# untitled.net
KiCad netlist of a schematic drawn in EAGLE
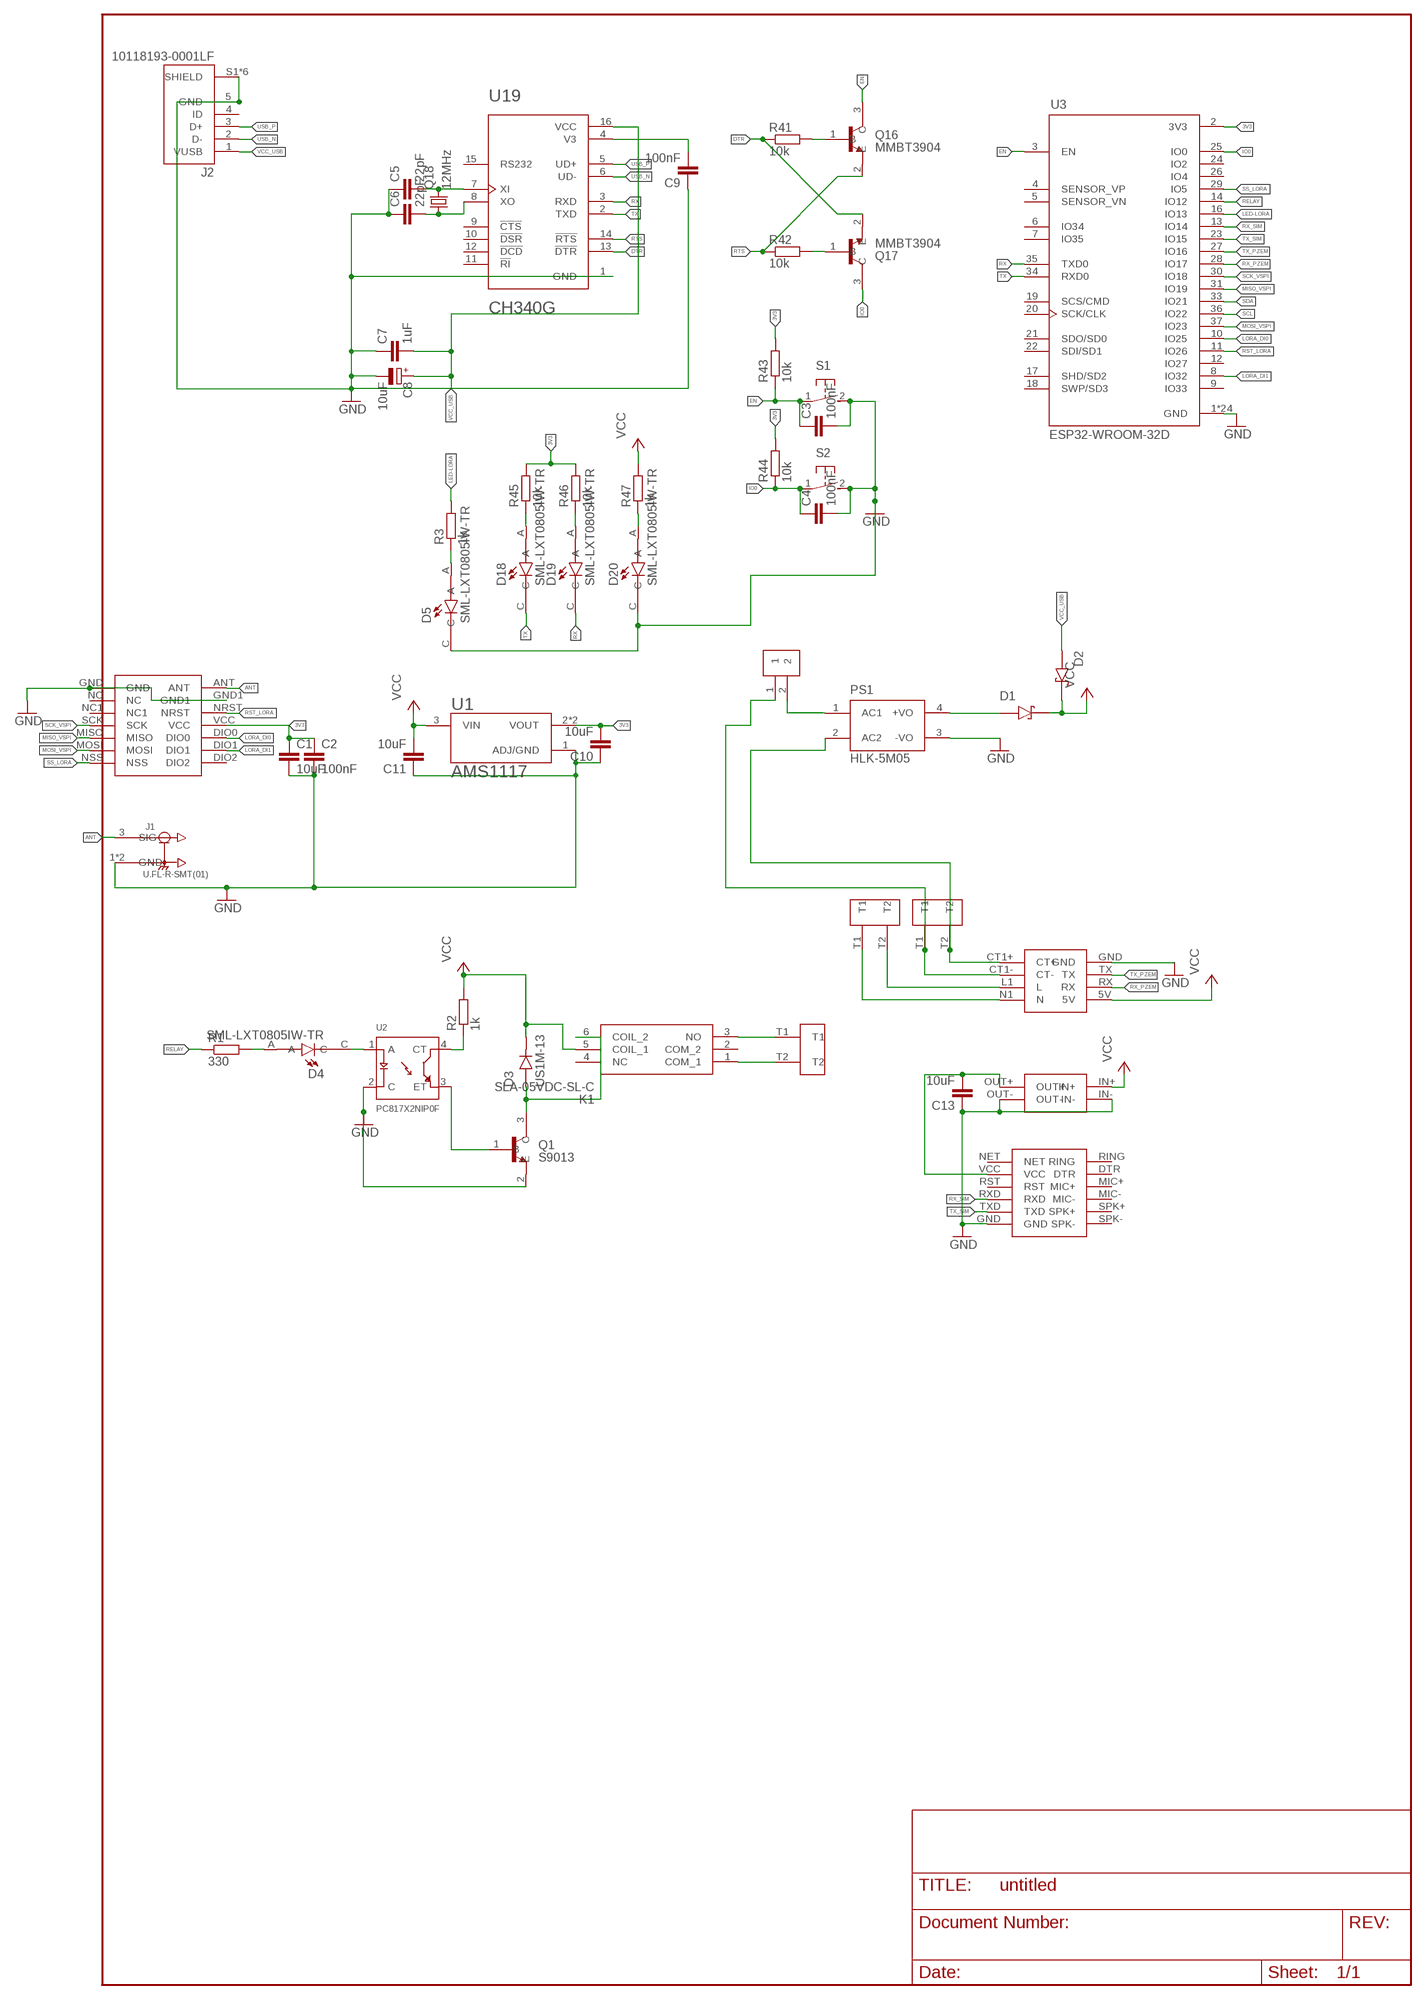
[diagram p0: schematic, sheet 1]

(export (version "E")
  (design (tool "Eeschema 10.0.6"))
  (components
    (comp (ref "C1")
      (value "10uF")
      (footprint "eagle-import:C0805K")
      (libsource (lib "eagle-import") (part "C-EUC0805K"))
    )
    (comp (ref "C2")
      (value "100nF")
      (footprint "eagle-import:C0805K")
      (libsource (lib "eagle-import") (part "C-EUC0805K"))
    )
    (comp (ref "C3")
      (value "100nF")
      (footprint "eagle-import:C0805K")
      (libsource (lib "eagle-import") (part "C-EUC0805K"))
    )
    (comp (ref "C4")
      (value "100nF")
      (footprint "eagle-import:C0805K")
      (libsource (lib "eagle-import") (part "C-EUC0805K"))
    )
    (comp (ref "C5")
      (value "22pF")
      (footprint "eagle-import:C0805K")
      (libsource (lib "eagle-import") (part "C-EUC0805K"))
    )
    (comp (ref "C6")
      (value "22pF")
      (footprint "eagle-import:C0805K")
      (libsource (lib "eagle-import") (part "C-EUC0805K"))
    )
    (comp (ref "C7")
      (value "1uF")
      (footprint "eagle-import:C0805K")
      (libsource (lib "eagle-import") (part "C-EUC0805K"))
    )
    (comp (ref "C8")
      (value "10uF")
      (footprint "eagle-import:153CLV-0505")
      (libsource (lib "eagle-import") (part "CPOL-EU153CLV-0505"))
    )
    (comp (ref "C9")
      (value "100nF")
      (footprint "eagle-import:C0805K")
      (libsource (lib "eagle-import") (part "C-EUC0805K"))
    )
    (comp (ref "C10")
      (value "10uF")
      (footprint "eagle-import:C0805K")
      (libsource (lib "eagle-import") (part "C-EUC0805K"))
    )
    (comp (ref "C11")
      (value "10uF")
      (footprint "eagle-import:C0805K")
      (libsource (lib "eagle-import") (part "C-EUC0805K"))
    )
    (comp (ref "C13")
      (value "10uF")
      (footprint "eagle-import:C0805K")
      (libsource (lib "eagle-import") (part "C-EUC0805K"))
    )
    (comp (ref "D1")
      (value "1N5819HW-7")
      (footprint "eagle-import:SOD3715X145N")
      (fields (field (name "MF") "Diodes Inc."))
      (libsource (lib "eagle-import") (part "1N5819HW-7"))
    )
    (comp (ref "D2")
      (value "1N5819HW-7")
      (footprint "eagle-import:SOD3715X145N")
      (fields (field (name "MF") "Diodes Inc."))
      (libsource (lib "eagle-import") (part "1N5819HW-7"))
    )
    (comp (ref "D3")
      (value "US1M-13")
      (footprint "eagle-import:DIOM5226X240N")
      (fields (field (name "MF") "Diodes Incorporated"))
      (libsource (lib "eagle-import") (part "US1M-13"))
    )
    (comp (ref "D4")
      (value "SML-LXT0805IW-TR")
      (footprint "eagle-import:LEDC2012X120N")
      (fields (field (name "MF") "Lumex Opto/Components"))
      (libsource (lib "eagle-import") (part "SML-LXT0805IW-TR"))
    )
    (comp (ref "D5")
      (value "SML-LXT0805IW-TR")
      (footprint "eagle-import:LEDC2012X120N")
      (fields (field (name "MF") "Lumex Opto/Components"))
      (libsource (lib "eagle-import") (part "SML-LXT0805IW-TR"))
    )
    (comp (ref "D18")
      (value "SML-LXT0805IW-TR")
      (footprint "eagle-import:LEDC2012X120N")
      (fields (field (name "MF") "Lumex Opto/Components"))
      (libsource (lib "eagle-import") (part "SML-LXT0805IW-TR"))
    )
    (comp (ref "D19")
      (value "SML-LXT0805IW-TR")
      (footprint "eagle-import:LEDC2012X120N")
      (fields (field (name "MF") "Lumex Opto/Components"))
      (libsource (lib "eagle-import") (part "SML-LXT0805IW-TR"))
    )
    (comp (ref "D20")
      (value "SML-LXT0805IW-TR")
      (footprint "eagle-import:LEDC2012X120N")
      (fields (field (name "MF") "Lumex Opto/Components"))
      (libsource (lib "eagle-import") (part "SML-LXT0805IW-TR"))
    )
    (comp (ref "FUSE-KOTAK1")
      (value "FUSE-KOTAK")
      (footprint "eagle-import:FUSE-KOTAK")
      (libsource (lib "eagle-import") (part "FUSE-KOTAK"))
    )
    (comp (ref "J1")
      (value "U.FL-R-SMT(01)")
      (footprint "eagle-import:HRS_U.FL-R-SMT(01)")
      (fields (field (name "MF") "Hirose"))
      (libsource (lib "eagle-import") (part "U.FL-R-SMT(01)"))
    )
    (comp (ref "J2")
      (value "10118193-0001LF")
      (footprint "eagle-import:FCI_10118193-0001LF")
      (fields (field (name "MF") "FCI"))
      (libsource (lib "eagle-import") (part "10118193-0001LF"))
    )
    (comp (ref "K1")
      (value "SLA-05VDC-SL-C")
      (footprint "eagle-import:SLA05VDCSLC")
      (libsource (lib "eagle-import") (part "SLA-05VDC-SL-C"))
    )
    (comp (ref "LORA-NICERF-V1")
      (value "LORA-NICERF-V2")
      (footprint "eagle-import:LORA-NICERF-V2")
      (libsource (lib "eagle-import") (part "LORA-NICERF-V2"))
    )
    (comp (ref "MINI1")
      (value "MINI360")
      (footprint "eagle-import:MINI360")
      (libsource (lib "eagle-import") (part "MINI360"))
    )
    (comp (ref "PS1")
      (value "HLK-5M05")
      (footprint "eagle-import:CONV_HLK-5M05")
      (fields (field (name "MF") "Hi-link"))
      (libsource (lib "eagle-import") (part "HLK-5M05"))
    )
    (comp (ref "PZEM004T1")
      (value "PZEM004T")
      (footprint "eagle-import:PZEM004T")
      (libsource (lib "eagle-import") (part "PZEM004T"))
    )
    (comp (ref "Q1")
      (value "S9013")
      (footprint "eagle-import:SOT95P240X120-3N")
      (fields (field (name "MF") "JCET"))
      (libsource (lib "eagle-import") (part "S9013"))
    )
    (comp (ref "Q16")
      (value "MMBT3904")
      (footprint "eagle-import:SOT95P240X120-3N")
      (fields (field (name "MF") "ON Semiconductor"))
      (libsource (lib "eagle-import") (part "MMBT3904"))
    )
    (comp (ref "Q17")
      (value "MMBT3904")
      (footprint "eagle-import:SOT95P240X120-3N")
      (fields (field (name "MF") "ON Semiconductor"))
      (libsource (lib "eagle-import") (part "MMBT3904"))
    )
    (comp (ref "Q18")
      (value "12MHz")
      (footprint "eagle-import:SM49")
      (libsource (lib "eagle-import") (part "CRYSTALSM49"))
    )
    (comp (ref "R1")
      (value "330")
      (footprint "eagle-import:R0805")
      (libsource (lib "eagle-import") (part "R-EU_R0805"))
    )
    (comp (ref "R2")
      (value "1k")
      (footprint "eagle-import:R0805")
      (libsource (lib "eagle-import") (part "R-EU_R0805"))
    )
    (comp (ref "R3")
      (value "1k")
      (footprint "eagle-import:R0805")
      (libsource (lib "eagle-import") (part "R-EU_R0805"))
    )
    (comp (ref "R41")
      (value "10k")
      (footprint "eagle-import:R0805")
      (libsource (lib "eagle-import") (part "R-EU_R0805"))
    )
    (comp (ref "R42")
      (value "10k")
      (footprint "eagle-import:R0805")
      (libsource (lib "eagle-import") (part "R-EU_R0805"))
    )
    (comp (ref "R43")
      (value "10k")
      (footprint "eagle-import:R0805")
      (libsource (lib "eagle-import") (part "R-EU_R0805"))
    )
    (comp (ref "R44")
      (value "10k")
      (footprint "eagle-import:R0805")
      (libsource (lib "eagle-import") (part "R-EU_R0805"))
    )
    (comp (ref "R45")
      (value "10k")
      (footprint "eagle-import:R0805")
      (libsource (lib "eagle-import") (part "R-EU_R0805"))
    )
    (comp (ref "R46")
      (value "10k")
      (footprint "eagle-import:R0805")
      (libsource (lib "eagle-import") (part "R-EU_R0805"))
    )
    (comp (ref "R47")
      (value "1k")
      (footprint "eagle-import:R0805")
      (libsource (lib "eagle-import") (part "R-EU_R0805"))
    )
    (comp (ref "S1")
      (value "31-XX")
      (footprint "eagle-import:B3F-31XX")
      (fields (field (name "MPN") "B3F-3100"))
      (libsource (lib "eagle-import") (part "31-XX"))
    )
    (comp (ref "S2")
      (value "31-XX")
      (footprint "eagle-import:B3F-31XX")
      (fields (field (name "MPN") "B3F-3100"))
      (libsource (lib "eagle-import") (part "31-XX"))
    )
    (comp (ref "SIM800L1")
      (value "SIM800L")
      (footprint "eagle-import:SIM800L")
      (libsource (lib "eagle-import") (part "SIM800L"))
    )
    (comp (ref "TB7.2")
      (value "TB7.62")
      (footprint "eagle-import:TB7.62")
      (libsource (lib "eagle-import") (part "TB7.62"))
    )
    (comp (ref "TB7.3")
      (value "TB7.62")
      (footprint "eagle-import:TB7.62")
      (libsource (lib "eagle-import") (part "TB7.62"))
    )
    (comp (ref "TB7.4")
      (value "TB7.62")
      (footprint "eagle-import:TB7.62")
      (libsource (lib "eagle-import") (part "TB7.62"))
    )
    (comp (ref "U1")
      (value "AMS1117")
      (footprint "eagle-import:SOT229P700X180-4N")
      (fields (field (name "MF") "Advanced Monolithic Systems"))
      (libsource (lib "eagle-import") (part "AMS1117"))
    )
    (comp (ref "U2")
      (value "PC817X2NIP0F")
      (footprint "eagle-import:SOT254P975X400-4N")
      (fields (field (name "MF") "Sharp Microelectronics"))
      (libsource (lib "eagle-import") (part "PC817X2NIP0F"))
    )
    (comp (ref "U3")
      (value "ESP32-WROOM-32D")
      (footprint "eagle-import:MODULE_ESP32-WROOM-32D")
      (fields (field (name "MF") "Espressif Systems"))
      (libsource (lib "eagle-import") (part "ESP32-WROOM-32D"))
    )
    (comp (ref "U19")
      (value "CH340G")
      (footprint "eagle-import:SOIC127P600X180-16N")
      (fields (field (name "MF") "WCH") (field (name "MP") "Ch340G"))
      (libsource (lib "eagle-import") (part "CH340G"))
    )
  )
  (nets
    (net (code "1") (name "3V3") (class "Default")
      (node (ref "C1") (pin "1") (pinfunction "1_1") (pintype "passive"))
      (node (ref "C10") (pin "2") (pinfunction "2_2") (pintype "passive"))
      (node (ref "C2") (pin "1") (pinfunction "1_1") (pintype "passive"))
      (node (ref "LORA-NICERF-V1") (pin "VCC") (pinfunction "VCC_VCC") (pintype "bidirectional"))
      (node (ref "R43") (pin "2") (pinfunction "2_2") (pintype "passive"))
      (node (ref "R44") (pin "2") (pinfunction "2_2") (pintype "passive"))
      (node (ref "R45") (pin "2") (pinfunction "2_2") (pintype "passive"))
      (node (ref "R46") (pin "2") (pinfunction "2_2") (pintype "passive"))
      (node (ref "U1") (pin "2") (pinfunction "VOUT_2") (pintype "output"))
      (node (ref "U1") (pin "4") (pinfunction "VOUT_4") (pintype "output"))
      (node (ref "U3") (pin "2") (pinfunction "3V3_2") (pintype "power_in"))
    )
    (net (code "2") (name "ANT") (class "Default")
      (node (ref "J1") (pin "3") (pinfunction "SIG_3") (pintype "passive"))
      (node (ref "LORA-NICERF-V1") (pin "ANT") (pinfunction "ANT_ANT") (pintype "bidirectional"))
    )
    (net (code "3") (name "DTR") (class "Default")
      (node (ref "Q17") (pin "2") (pinfunction "E_2") (pintype "passive"))
      (node (ref "R41") (pin "1") (pinfunction "1_1") (pintype "passive"))
      (node (ref "U19") (pin "13") (pinfunction "~{DTR}_13") (pintype "output"))
    )
    (net (code "4") (name "EN") (class "Default")
      (node (ref "C3") (pin "1") (pinfunction "1_1") (pintype "passive"))
      (node (ref "Q16") (pin "3") (pinfunction "C_3") (pintype "passive"))
      (node (ref "R43") (pin "1") (pinfunction "1_1") (pintype "passive"))
      (node (ref "S1") (pin "1") (pinfunction "P_1") (pintype "passive"))
      (node (ref "U3") (pin "3") (pinfunction "EN_3") (pintype "input"))
    )
    (net (code "5") (name "GND") (class "Default")
      (node (ref "C1") (pin "2") (pinfunction "2_2") (pintype "passive"))
      (node (ref "C10") (pin "1") (pinfunction "1_1") (pintype "passive"))
      (node (ref "C11") (pin "1") (pinfunction "1_1") (pintype "passive"))
      (node (ref "C13") (pin "1") (pinfunction "1_1") (pintype "passive"))
      (node (ref "C2") (pin "2") (pinfunction "2_2") (pintype "passive"))
      (node (ref "C3") (pin "2") (pinfunction "2_2") (pintype "passive"))
      (node (ref "C4") (pin "2") (pinfunction "2_2") (pintype "passive"))
      (node (ref "C5") (pin "1") (pinfunction "1_1") (pintype "passive"))
      (node (ref "C6") (pin "1") (pinfunction "1_1") (pintype "passive"))
      (node (ref "C7") (pin "1") (pinfunction "1_1") (pintype "passive"))
      (node (ref "C8") (pin "-") (pinfunction "-_-") (pintype "passive"))
      (node (ref "C9") (pin "1") (pinfunction "1_1") (pintype "passive"))
      (node (ref "D20") (pin "C") (pinfunction "C_C") (pintype "passive"))
      (node (ref "D5") (pin "C") (pinfunction "C_C") (pintype "passive"))
      (node (ref "J1") (pin "1") (pinfunction "GND_1") (pintype "passive"))
      (node (ref "J1") (pin "2") (pinfunction "GND_2") (pintype "passive"))
      (node (ref "J2") (pin "5") (pinfunction "GND_5") (pintype "passive"))
      (node (ref "J2") (pin "S1") (pinfunction "SHIELD_S1") (pintype "passive"))
      (node (ref "J2") (pin "S2") (pinfunction "SHIELD_S2") (pintype "passive"))
      (node (ref "J2") (pin "S3") (pinfunction "SHIELD_S3") (pintype "passive"))
      (node (ref "J2") (pin "S4") (pinfunction "SHIELD_S4") (pintype "passive"))
      (node (ref "J2") (pin "S5") (pinfunction "SHIELD_S5") (pintype "passive"))
      (node (ref "J2") (pin "S6") (pinfunction "SHIELD_S6") (pintype "passive"))
      (node (ref "LORA-NICERF-V1") (pin "GND") (pinfunction "GND_GND") (pintype "bidirectional"))
      (node (ref "LORA-NICERF-V1") (pin "GND1") (pinfunction "GND1_GND1") (pintype "bidirectional"))
      (node (ref "MINI1") (pin "IN-") (pinfunction "IN-_IN-") (pintype "bidirectional"))
      (node (ref "MINI1") (pin "OUT-") (pinfunction "OUT-_OUT-") (pintype "bidirectional"))
      (node (ref "PS1") (pin "3") (pinfunction "-VO_3") (pintype "output"))
      (node (ref "PZEM004T1") (pin "GND") (pinfunction "GND_GND") (pintype "bidirectional"))
      (node (ref "Q1") (pin "2") (pinfunction "E_2") (pintype "passive"))
      (node (ref "S1") (pin "2") (pinfunction "S_2") (pintype "passive"))
      (node (ref "S2") (pin "2") (pinfunction "S_2") (pintype "passive"))
      (node (ref "SIM800L1") (pin "GND") (pinfunction "GND_GND") (pintype "bidirectional"))
      (node (ref "U1") (pin "1") (pinfunction "ADJ/GND_1") (pintype "power_in"))
      (node (ref "U19") (pin "1") (pinfunction "GND_1") (pintype "power_in"))
      (node (ref "U2") (pin "2") (pinfunction "C_2") (pintype "passive"))
      (node (ref "U3") (pin "1") (pinfunction "GND_1") (pintype "power_in"))
      (node (ref "U3") (pin "15") (pinfunction "GND_15") (pintype "power_in"))
      (node (ref "U3") (pin "38") (pinfunction "GND_38") (pintype "power_in"))
      (node (ref "U3") (pin "39_1") (pinfunction "GND_39_1") (pintype "power_in"))
      (node (ref "U3") (pin "39_10") (pinfunction "GND_39_10") (pintype "power_in"))
      (node (ref "U3") (pin "39_11") (pinfunction "GND_39_11") (pintype "power_in"))
      (node (ref "U3") (pin "39_12") (pinfunction "GND_39_12") (pintype "power_in"))
      (node (ref "U3") (pin "39_13") (pinfunction "GND_39_13") (pintype "power_in"))
      (node (ref "U3") (pin "39_14") (pinfunction "GND_39_14") (pintype "power_in"))
      (node (ref "U3") (pin "39_15") (pinfunction "GND_39_15") (pintype "power_in"))
      (node (ref "U3") (pin "39_16") (pinfunction "GND_39_16") (pintype "power_in"))
      (node (ref "U3") (pin "39_17") (pinfunction "GND_39_17") (pintype "power_in"))
      (node (ref "U3") (pin "39_18") (pinfunction "GND_39_18") (pintype "power_in"))
      (node (ref "U3") (pin "39_19") (pinfunction "GND_39_19") (pintype "power_in"))
      (node (ref "U3") (pin "39_2") (pinfunction "GND_39_2") (pintype "power_in"))
      (node (ref "U3") (pin "39_20") (pinfunction "GND_39_20") (pintype "power_in"))
      (node (ref "U3") (pin "39_21") (pinfunction "GND_39_21") (pintype "power_in"))
      (node (ref "U3") (pin "39_3") (pinfunction "GND_39_3") (pintype "power_in"))
      (node (ref "U3") (pin "39_4") (pinfunction "GND_39_4") (pintype "power_in"))
      (node (ref "U3") (pin "39_5") (pinfunction "GND_39_5") (pintype "power_in"))
      (node (ref "U3") (pin "39_6") (pinfunction "GND_39_6") (pintype "power_in"))
      (node (ref "U3") (pin "39_7") (pinfunction "GND_39_7") (pintype "power_in"))
      (node (ref "U3") (pin "39_8") (pinfunction "GND_39_8") (pintype "power_in"))
      (node (ref "U3") (pin "39_9") (pinfunction "GND_39_9") (pintype "power_in"))
    )
    (net (code "6") (name "IO0") (class "Default")
      (node (ref "C4") (pin "1") (pinfunction "1_1") (pintype "passive"))
      (node (ref "Q17") (pin "3") (pinfunction "C_3") (pintype "passive"))
      (node (ref "R44") (pin "1") (pinfunction "1_1") (pintype "passive"))
      (node (ref "S2") (pin "1") (pinfunction "P_1") (pintype "passive"))
      (node (ref "U3") (pin "25") (pinfunction "IO0_25") (pintype "bidirectional"))
    )
    (net (code "7") (name "LED-LORA") (class "Default")
      (node (ref "R3") (pin "2") (pinfunction "2_2") (pintype "passive"))
      (node (ref "U3") (pin "16") (pinfunction "IO13_16") (pintype "bidirectional"))
    )
    (net (code "8") (name "LORA_DI0") (class "Default")
      (node (ref "LORA-NICERF-V1") (pin "DIO0") (pinfunction "DIO0_DIO0") (pintype "bidirectional"))
      (node (ref "U3") (pin "10") (pinfunction "IO25_10") (pintype "bidirectional"))
    )
    (net (code "9") (name "LORA_DI1") (class "Default")
      (node (ref "LORA-NICERF-V1") (pin "DIO1") (pinfunction "DIO1_DIO1") (pintype "bidirectional"))
      (node (ref "U3") (pin "8") (pinfunction "IO32_8") (pintype "bidirectional"))
    )
    (net (code "10") (name "MISO_VSPI") (class "Default")
      (node (ref "LORA-NICERF-V1") (pin "MISO") (pinfunction "MISO_MISO") (pintype "bidirectional"))
      (node (ref "U3") (pin "31") (pinfunction "IO19_31") (pintype "bidirectional"))
    )
    (net (code "11") (name "MOSI_VSPI") (class "Default")
      (node (ref "LORA-NICERF-V1") (pin "MOSI") (pinfunction "MOSI_MOSI") (pintype "bidirectional"))
      (node (ref "U3") (pin "37") (pinfunction "IO23_37") (pintype "bidirectional"))
    )
    (net (code "12") (name "Net-(C13-Pad2)") (class "Default")
      (node (ref "C13") (pin "2") (pinfunction "2_2") (pintype "passive"))
      (node (ref "MINI1") (pin "OUT+") (pinfunction "OUT+_OUT+") (pintype "bidirectional"))
      (node (ref "SIM800L1") (pin "VCC") (pinfunction "VCC_VCC") (pintype "bidirectional"))
    )
    (net (code "13") (name "Net-(D4-PadA)") (class "Default")
      (node (ref "D4") (pin "A") (pinfunction "A_A") (pintype "passive"))
      (node (ref "R1") (pin "2") (pinfunction "2_2") (pintype "passive"))
    )
    (net (code "14") (name "Net-(D5-PadA)") (class "Default")
      (node (ref "D5") (pin "A") (pinfunction "A_A") (pintype "passive"))
      (node (ref "R3") (pin "1") (pinfunction "1_1") (pintype "passive"))
    )
    (net (code "15") (name "Net-(D18-PadA)") (class "Default")
      (node (ref "D18") (pin "A") (pinfunction "A_A") (pintype "passive"))
      (node (ref "R45") (pin "1") (pinfunction "1_1") (pintype "passive"))
    )
    (net (code "16") (name "Net-(D19-PadA)") (class "Default")
      (node (ref "D19") (pin "A") (pinfunction "A_A") (pintype "passive"))
      (node (ref "R46") (pin "1") (pinfunction "1_1") (pintype "passive"))
    )
    (net (code "17") (name "Net-(D20-PadA)") (class "Default")
      (node (ref "D20") (pin "A") (pinfunction "A_A") (pintype "passive"))
      (node (ref "R47") (pin "1") (pinfunction "1_1") (pintype "passive"))
    )
    (net (code "18") (name "Net-(K1-COIL_2)") (class "Default")
      (node (ref "D3") (pin "A") (pinfunction "A_A") (pintype "passive"))
      (node (ref "K1") (pin "6") (pinfunction "COIL_2_6") (pintype "bidirectional"))
      (node (ref "Q1") (pin "3") (pinfunction "C_3") (pintype "passive"))
    )
    (net (code "19") (name "Net-(K1-COM_1)") (class "Default")
      (node (ref "K1") (pin "1") (pinfunction "COM_1_1") (pintype "bidirectional"))
      (node (ref "TB7.2") (pin "T2") (pinfunction "T2_T2") (pintype "bidirectional"))
    )
    (net (code "20") (name "Net-(K1-NO)") (class "Default")
      (node (ref "K1") (pin "3") (pinfunction "NO_3") (pintype "bidirectional"))
      (node (ref "TB7.2") (pin "T1") (pinfunction "T1_T1") (pintype "bidirectional"))
    )
    (net (code "21") (name "Net-(PS1-+VO)") (class "Default")
      (node (ref "D1") (pin "A") (pinfunction "A_A") (pintype "passive"))
      (node (ref "PS1") (pin "4") (pinfunction "+VO_4") (pintype "output"))
    )
    (net (code "22") (name "Net-(PS1-AC1)") (class "Default")
      (node (ref "FUSE-KOTAK1") (pin "2") (pinfunction "2_2") (pintype "bidirectional"))
      (node (ref "PS1") (pin "1") (pinfunction "AC1_1") (pintype "input"))
    )
    (net (code "23") (name "Net-(PS1-AC2)") (class "Default")
      (node (ref "PS1") (pin "2") (pinfunction "AC2_2") (pintype "input"))
      (node (ref "PZEM004T1") (pin "CT1+") (pinfunction "CT+_CT1+") (pintype "bidirectional"))
      (node (ref "TB7.3") (pin "T2") (pinfunction "T2_T2") (pintype "bidirectional"))
    )
    (net (code "24") (name "Net-(PZEM004T1-CT-)") (class "Default")
      (node (ref "FUSE-KOTAK1") (pin "1") (pinfunction "1_1") (pintype "bidirectional"))
      (node (ref "PZEM004T1") (pin "CT1-") (pinfunction "CT-_CT1-") (pintype "bidirectional"))
      (node (ref "TB7.3") (pin "T1") (pinfunction "T1_T1") (pintype "bidirectional"))
    )
    (net (code "25") (name "Net-(PZEM004T1-L)") (class "Default")
      (node (ref "PZEM004T1") (pin "L1") (pinfunction "L_L1") (pintype "bidirectional"))
      (node (ref "TB7.4") (pin "T2") (pinfunction "T2_T2") (pintype "bidirectional"))
    )
    (net (code "26") (name "Net-(PZEM004T1-N)") (class "Default")
      (node (ref "PZEM004T1") (pin "N1") (pinfunction "N_N1") (pintype "bidirectional"))
      (node (ref "TB7.4") (pin "T1") (pinfunction "T1_T1") (pintype "bidirectional"))
    )
    (net (code "27") (name "Net-(Q1-B)") (class "Default")
      (node (ref "Q1") (pin "1") (pinfunction "B_1") (pintype "passive"))
      (node (ref "U2") (pin "3") (pinfunction "ET_3") (pintype "passive"))
    )
    (net (code "28") (name "Net-(Q16-B)") (class "Default")
      (node (ref "Q16") (pin "1") (pinfunction "B_1") (pintype "passive"))
      (node (ref "R41") (pin "2") (pinfunction "2_2") (pintype "passive"))
    )
    (net (code "29") (name "Net-(Q17-B)") (class "Default")
      (node (ref "Q17") (pin "1") (pinfunction "B_1") (pintype "passive"))
      (node (ref "R42") (pin "2") (pinfunction "2_2") (pintype "passive"))
    )
    (net (code "30") (name "Net-(U2-A)") (class "Default")
      (node (ref "D4") (pin "C") (pinfunction "C_C") (pintype "passive"))
      (node (ref "U2") (pin "1") (pinfunction "A_1") (pintype "passive"))
    )
    (net (code "31") (name "Net-(U2-CT)") (class "Default")
      (node (ref "R2") (pin "1") (pinfunction "1_1") (pintype "passive"))
      (node (ref "U2") (pin "4") (pinfunction "CT_4") (pintype "passive"))
    )
    (net (code "32") (name "Net-(U19-V3)") (class "Default")
      (node (ref "C9") (pin "2") (pinfunction "2_2") (pintype "passive"))
      (node (ref "U19") (pin "4") (pinfunction "V3_4") (pintype "power_in"))
    )
    (net (code "33") (name "Net-(U19-XI)") (class "Default")
      (node (ref "C5") (pin "2") (pinfunction "2_2") (pintype "passive"))
      (node (ref "Q18") (pin "2") (pinfunction "2_2") (pintype "passive"))
      (node (ref "U19") (pin "7") (pinfunction "XI_7") (pintype "input"))
    )
    (net (code "34") (name "Net-(U19-XO)") (class "Default")
      (node (ref "C6") (pin "2") (pinfunction "2_2") (pintype "passive"))
      (node (ref "Q18") (pin "1") (pinfunction "1_1") (pintype "passive"))
      (node (ref "U19") (pin "8") (pinfunction "XO_8") (pintype "output"))
    )
    (net (code "35") (name "RELAY") (class "Default")
      (node (ref "R1") (pin "1") (pinfunction "1_1") (pintype "passive"))
      (node (ref "U3") (pin "14") (pinfunction "IO12_14") (pintype "bidirectional"))
    )
    (net (code "36") (name "RST_LORA") (class "Default")
      (node (ref "LORA-NICERF-V1") (pin "NRST") (pinfunction "NRST_NRST") (pintype "bidirectional"))
      (node (ref "U3") (pin "11") (pinfunction "IO26_11") (pintype "bidirectional"))
    )
    (net (code "37") (name "RTS") (class "Default")
      (node (ref "Q16") (pin "2") (pinfunction "E_2") (pintype "passive"))
      (node (ref "R42") (pin "1") (pinfunction "1_1") (pintype "passive"))
      (node (ref "U19") (pin "14") (pinfunction "~{RTS}_14") (pintype "output"))
    )
    (net (code "38") (name "RX") (class "Default")
      (node (ref "D19") (pin "C") (pinfunction "C_C") (pintype "passive"))
      (node (ref "U19") (pin "3") (pinfunction "RXD_3") (pintype "input"))
      (node (ref "U3") (pin "35") (pinfunction "TXD0_35") (pintype "bidirectional"))
    )
    (net (code "39") (name "RX_PZEM") (class "Default")
      (node (ref "PZEM004T1") (pin "RX") (pinfunction "RX_RX") (pintype "bidirectional"))
      (node (ref "U3") (pin "28") (pinfunction "IO17_28") (pintype "bidirectional"))
    )
    (net (code "40") (name "RX_SIM") (class "Default")
      (node (ref "SIM800L1") (pin "RXD") (pinfunction "RXD_RXD") (pintype "bidirectional"))
      (node (ref "U3") (pin "13") (pinfunction "IO14_13") (pintype "bidirectional"))
    )
    (net (code "41") (name "SCK_VSPI") (class "Default")
      (node (ref "LORA-NICERF-V1") (pin "SCK") (pinfunction "SCK_SCK") (pintype "bidirectional"))
      (node (ref "U3") (pin "30") (pinfunction "IO18_30") (pintype "bidirectional"))
    )
    (net (code "42") (name "SCL") (class "Default")
      (node (ref "U3") (pin "36") (pinfunction "IO22_36") (pintype "bidirectional"))
    )
    (net (code "43") (name "SDA") (class "Default")
      (node (ref "U3") (pin "33") (pinfunction "IO21_33") (pintype "bidirectional"))
    )
    (net (code "44") (name "SS_LORA") (class "Default")
      (node (ref "LORA-NICERF-V1") (pin "NSS") (pinfunction "NSS_NSS") (pintype "bidirectional"))
      (node (ref "U3") (pin "29") (pinfunction "IO5_29") (pintype "bidirectional"))
    )
    (net (code "45") (name "TX") (class "Default")
      (node (ref "D18") (pin "C") (pinfunction "C_C") (pintype "passive"))
      (node (ref "U19") (pin "2") (pinfunction "TXD_2") (pintype "output"))
      (node (ref "U3") (pin "34") (pinfunction "RXD0_34") (pintype "bidirectional"))
    )
    (net (code "46") (name "TX_PZEM") (class "Default")
      (node (ref "PZEM004T1") (pin "TX") (pinfunction "TX_TX") (pintype "bidirectional"))
      (node (ref "U3") (pin "27") (pinfunction "IO16_27") (pintype "bidirectional"))
    )
    (net (code "47") (name "TX_SIM") (class "Default")
      (node (ref "SIM800L1") (pin "TXD") (pinfunction "TXD_TXD") (pintype "bidirectional"))
      (node (ref "U3") (pin "23") (pinfunction "IO15_23") (pintype "bidirectional"))
    )
    (net (code "48") (name "USB_N") (class "Default")
      (node (ref "J2") (pin "2") (pinfunction "D-_2") (pintype "passive"))
      (node (ref "U19") (pin "6") (pinfunction "UD-_6") (pintype "bidirectional"))
    )
    (net (code "49") (name "USB_P") (class "Default")
      (node (ref "J2") (pin "3") (pinfunction "D+_3") (pintype "passive"))
      (node (ref "U19") (pin "5") (pinfunction "UD+_5") (pintype "bidirectional"))
    )
    (net (code "50") (name "VCC") (class "Default")
      (node (ref "C11") (pin "2") (pinfunction "2_2") (pintype "passive"))
      (node (ref "D1") (pin "C") (pinfunction "K_C") (pintype "passive"))
      (node (ref "D2") (pin "C") (pinfunction "K_C") (pintype "passive"))
      (node (ref "D3") (pin "C") (pinfunction "K_C") (pintype "passive"))
      (node (ref "K1") (pin "5") (pinfunction "COIL_1_5") (pintype "bidirectional"))
      (node (ref "MINI1") (pin "IN+") (pinfunction "IN+_IN+") (pintype "bidirectional"))
      (node (ref "PZEM004T1") (pin "5V") (pinfunction "5V_5V") (pintype "bidirectional"))
      (node (ref "R2") (pin "2") (pinfunction "2_2") (pintype "passive"))
      (node (ref "R47") (pin "2") (pinfunction "2_2") (pintype "passive"))
      (node (ref "U1") (pin "3") (pinfunction "VIN_3") (pintype "input"))
    )
    (net (code "51") (name "VCC_USB") (class "Default")
      (node (ref "C7") (pin "2") (pinfunction "2_2") (pintype "passive"))
      (node (ref "C8") (pin "+") (pinfunction "+_+") (pintype "passive"))
      (node (ref "D2") (pin "A") (pinfunction "A_A") (pintype "passive"))
      (node (ref "J2") (pin "1") (pinfunction "VUSB_1") (pintype "passive"))
      (node (ref "U19") (pin "16") (pinfunction "VCC_16") (pintype "power_in"))
    )
    (net (code "52") (name "unconnected-(J2-ID-Pad4)") (class "Default")
      (node (ref "J2") (pin "4") (pinfunction "ID_4") (pintype "passive"))
    )
    (net (code "53") (name "unconnected-(K1-COM_2-Pad2)") (class "Default")
      (node (ref "K1") (pin "2") (pinfunction "COM_2_2") (pintype "bidirectional"))
    )
    (net (code "54") (name "unconnected-(K1-NC-Pad4)") (class "Default")
      (node (ref "K1") (pin "4") (pinfunction "NC_4") (pintype "no_connect"))
    )
    (net (code "55") (name "unconnected-(LORA-NICERF-V1-PadDIO2)") (class "Default")
      (node (ref "LORA-NICERF-V1") (pin "DIO2") (pinfunction "DIO2_DIO2") (pintype "bidirectional"))
    )
    (net (code "56") (name "unconnected-(LORA-NICERF-V1-PadNC)") (class "Default")
      (node (ref "LORA-NICERF-V1") (pin "NC") (pinfunction "NC_NC") (pintype "bidirectional"))
    )
    (net (code "57") (name "unconnected-(LORA-NICERF-V1-PadNC1)") (class "Default")
      (node (ref "LORA-NICERF-V1") (pin "NC1") (pinfunction "NC1_NC1") (pintype "bidirectional"))
    )
    (net (code "58") (name "unconnected-(SIM800L1-PadDTR)") (class "Default")
      (node (ref "SIM800L1") (pin "DTR") (pinfunction "DTR_DTR") (pintype "bidirectional"))
    )
    (net (code "59") (name "unconnected-(SIM800L1-PadMIC+)") (class "Default")
      (node (ref "SIM800L1") (pin "MIC+") (pinfunction "MIC+_MIC+") (pintype "bidirectional"))
    )
    (net (code "60") (name "unconnected-(SIM800L1-PadMIC-)") (class "Default")
      (node (ref "SIM800L1") (pin "MIC-") (pinfunction "MIC-_MIC-") (pintype "bidirectional"))
    )
    (net (code "61") (name "unconnected-(SIM800L1-PadNET)") (class "Default")
      (node (ref "SIM800L1") (pin "NET") (pinfunction "NET_NET") (pintype "bidirectional"))
    )
    (net (code "62") (name "unconnected-(SIM800L1-PadRING)") (class "Default")
      (node (ref "SIM800L1") (pin "RING") (pinfunction "RING_RING") (pintype "bidirectional"))
    )
    (net (code "63") (name "unconnected-(SIM800L1-PadRST)") (class "Default")
      (node (ref "SIM800L1") (pin "RST") (pinfunction "RST_RST") (pintype "bidirectional"))
    )
    (net (code "64") (name "unconnected-(SIM800L1-PadSPK+)") (class "Default")
      (node (ref "SIM800L1") (pin "SPK+") (pinfunction "SPK+_SPK+") (pintype "bidirectional"))
    )
    (net (code "65") (name "unconnected-(SIM800L1-PadSPK-)") (class "Default")
      (node (ref "SIM800L1") (pin "SPK-") (pinfunction "SPK-_SPK-") (pintype "bidirectional"))
    )
    (net (code "66") (name "unconnected-(U3-IO2-Pad24)") (class "Default")
      (node (ref "U3") (pin "24") (pinfunction "IO2_24") (pintype "bidirectional"))
    )
    (net (code "67") (name "unconnected-(U3-IO4-Pad26)") (class "Default")
      (node (ref "U3") (pin "26") (pinfunction "IO4_26") (pintype "bidirectional"))
    )
    (net (code "68") (name "unconnected-(U3-IO27-Pad12)") (class "Default")
      (node (ref "U3") (pin "12") (pinfunction "IO27_12") (pintype "bidirectional"))
    )
    (net (code "69") (name "unconnected-(U3-IO33-Pad9)") (class "Default")
      (node (ref "U3") (pin "9") (pinfunction "IO33_9") (pintype "bidirectional"))
    )
    (net (code "70") (name "unconnected-(U3-IO34-Pad6)") (class "Default")
      (node (ref "U3") (pin "6") (pinfunction "IO34_6") (pintype "input"))
    )
    (net (code "71") (name "unconnected-(U3-IO35-Pad7)") (class "Default")
      (node (ref "U3") (pin "7") (pinfunction "IO35_7") (pintype "input"))
    )
    (net (code "72") (name "unconnected-(U3-SCK{slash}CLK-Pad20)") (class "Default")
      (node (ref "U3") (pin "20") (pinfunction "SCK/CLK_20") (pintype "bidirectional"))
    )
    (net (code "73") (name "unconnected-(U3-SCS{slash}CMD-Pad19)") (class "Default")
      (node (ref "U3") (pin "19") (pinfunction "SCS/CMD_19") (pintype "bidirectional"))
    )
    (net (code "74") (name "unconnected-(U3-SDI{slash}SD1-Pad22)") (class "Default")
      (node (ref "U3") (pin "22") (pinfunction "SDI/SD1_22") (pintype "bidirectional"))
    )
    (net (code "75") (name "unconnected-(U3-SDO{slash}SD0-Pad21)") (class "Default")
      (node (ref "U3") (pin "21") (pinfunction "SDO/SD0_21") (pintype "bidirectional"))
    )
    (net (code "76") (name "unconnected-(U3-SENSOR_VN-Pad5)") (class "Default")
      (node (ref "U3") (pin "5") (pinfunction "SENSOR_VN_5") (pintype "input"))
    )
    (net (code "77") (name "unconnected-(U3-SENSOR_VP-Pad4)") (class "Default")
      (node (ref "U3") (pin "4") (pinfunction "SENSOR_VP_4") (pintype "input"))
    )
    (net (code "78") (name "unconnected-(U3-SHD{slash}SD2-Pad17)") (class "Default")
      (node (ref "U3") (pin "17") (pinfunction "SHD/SD2_17") (pintype "bidirectional"))
    )
    (net (code "79") (name "unconnected-(U3-SWP{slash}SD3-Pad18)") (class "Default")
      (node (ref "U3") (pin "18") (pinfunction "SWP/SD3_18") (pintype "bidirectional"))
    )
    (net (code "80") (name "unconnected-(U19-RS232-Pad15)") (class "Default")
      (node (ref "U19") (pin "15") (pinfunction "RS232_15") (pintype "input"))
    )
    (net (code "81") (name "unconnected-(U19-~{CTS}-Pad9)") (class "Default")
      (node (ref "U19") (pin "9") (pinfunction "~{CTS}_9") (pintype "input"))
    )
    (net (code "82") (name "unconnected-(U19-~{DCD}-Pad12)") (class "Default")
      (node (ref "U19") (pin "12") (pinfunction "~{DCD}_12") (pintype "input"))
    )
    (net (code "83") (name "unconnected-(U19-~{DSR}-Pad10)") (class "Default")
      (node (ref "U19") (pin "10") (pinfunction "~{DSR}_10") (pintype "input"))
    )
    (net (code "84") (name "unconnected-(U19-~{RI}-Pad11)") (class "Default")
      (node (ref "U19") (pin "11") (pinfunction "~{RI}_11") (pintype "input"))
    )
  )
)
